# QuadSwitch.net
KiCad netlist of a schematic drawn in Altium Designer
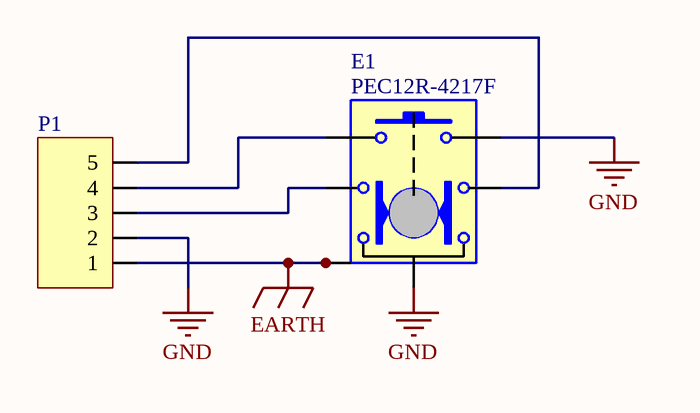
[diagram p0: QuadSwitch.SchDoc]

(export (version "E")
  (design (tool "Eeschema 10.0.6"))
  (components
    (comp (ref "E1")
      (value "PEC12R-4217F")
      (footprint "RotaryEncoder - PEC12R")
      (description "Rotary Encoder Bourns 17.5 mm shaft")
      (libsource (lib "MySchLib") (part "Rotary Encoder - PEC12R-4217F"))
    )
    (comp (ref "P1")
      (value "Header, 5-Pin")
      (footprint "HDR1X5S")
      (fields (field (name "PUBLISHER") "Altium Limited"))
      (libsource (lib "MyLibrary") (part "Header 1x5"))
    )
  )
  (nets
    (net (code "1") (name "EARTH") (class "Default")
      (node (ref "E1") (pin "SHLD1") (pinfunction "SHLD1_SHLD1") (pintype "passive"))
      (node (ref "E1") (pin "SHLD2") (pinfunction "SHLD2_SHLD2") (pintype "passive"))
      (node (ref "P1") (pin "1") (pinfunction "1_1") (pintype "passive"))
    )
    (net (code "2") (name "GND") (class "Default")
      (node (ref "E1") (pin "Common") (pinfunction "Common_Common") (pintype "passive"))
      (node (ref "E1") (pin "SW1") (pinfunction "SW1_SW1") (pintype "passive"))
      (node (ref "P1") (pin "2") (pinfunction "2_2") (pintype "passive"))
    )
    (net (code "3") (name "Net-(E1-PadPhaseA)") (class "Default")
      (node (ref "E1") (pin "PhaseA") (pinfunction "PhaseA_PhaseA") (pintype "passive"))
      (node (ref "P1") (pin "5") (pinfunction "5_5") (pintype "passive"))
    )
    (net (code "4") (name "Net-(E1-PadPhaseB)") (class "Default")
      (node (ref "E1") (pin "PhaseB") (pinfunction "PhaseB_PhaseB") (pintype "passive"))
      (node (ref "P1") (pin "3") (pinfunction "3_3") (pintype "passive"))
    )
    (net (code "5") (name "Net-(E1-PadSW2)") (class "Default")
      (node (ref "E1") (pin "SW2") (pinfunction "SW2_SW2") (pintype "passive"))
      (node (ref "P1") (pin "4") (pinfunction "4_4") (pintype "passive"))
    )
  )
)
